# Sheet_BEEE.net
KiCad netlist of a schematic drawn in Altium Designer
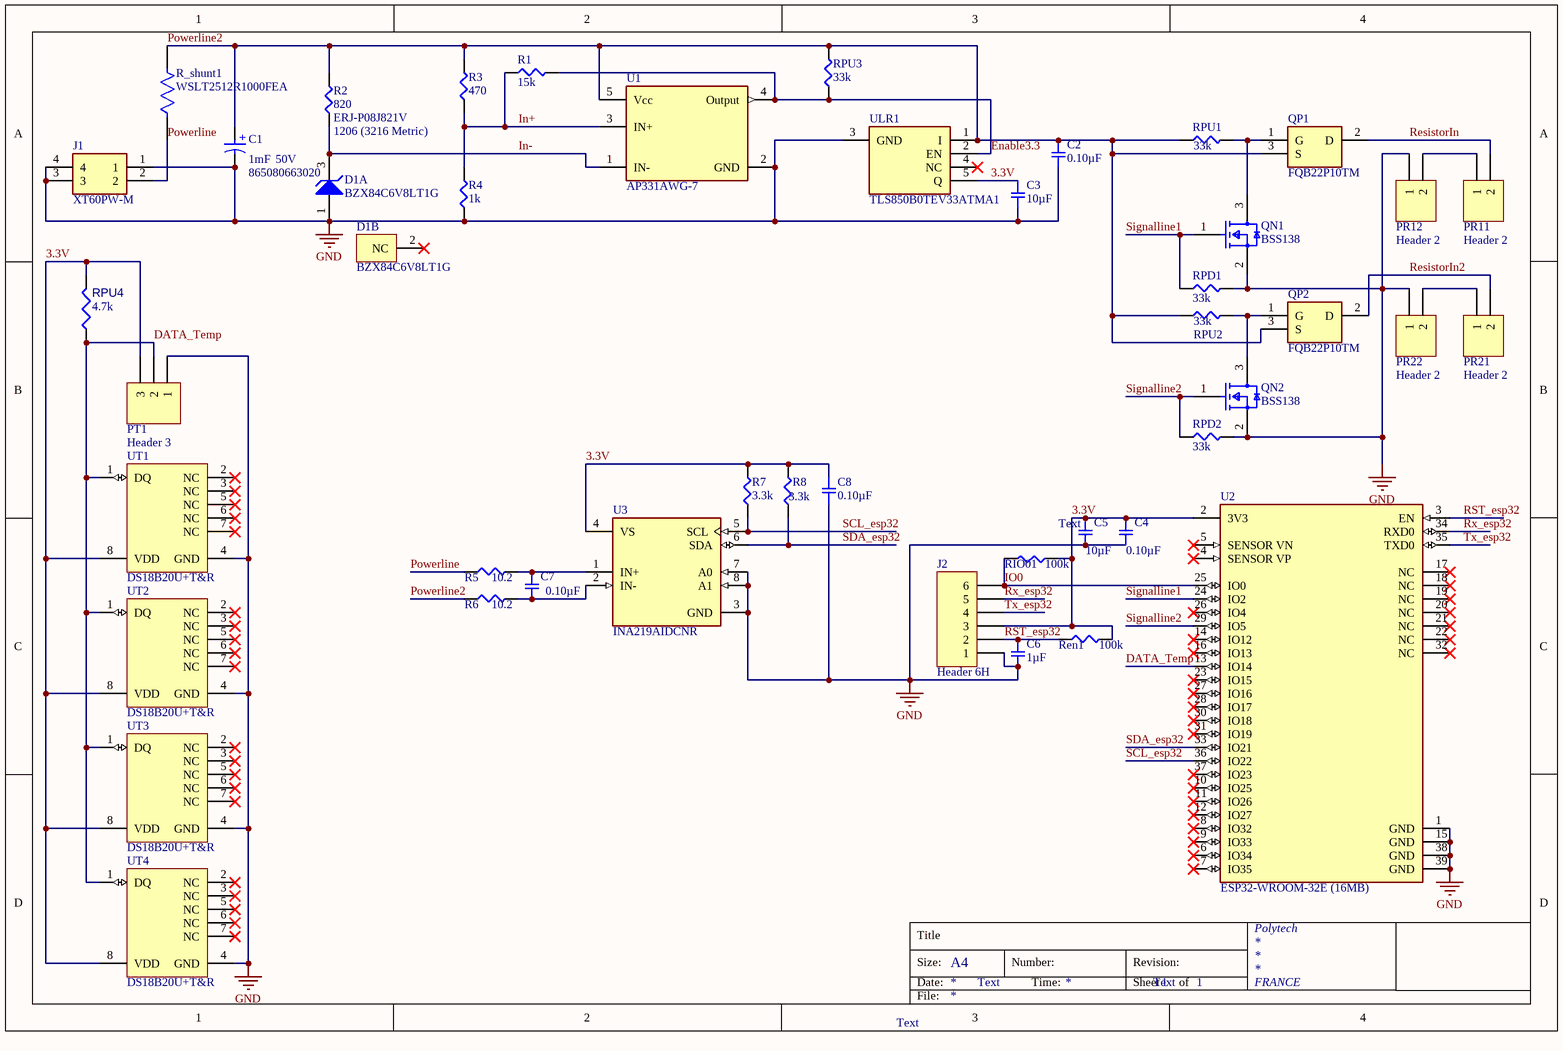
[diagram p0: Sheet_BEEE.SchDoc]

(export (version "E")
  (design (tool "Eeschema 10.0.6"))
  (components
    (comp (ref "C1")
      (value "865080663020")
      (footprint "WCAP-ASLI_D16H17")
      (description "865080663020 WCAP-ASLI Aluminum Electrolytic Capacitors")
      (fields
        (field (name "CAPACITANCE") "1mF")
        (field (name "VOLTAGE RATING") "50V")
        (field (name "TOLERANCE") "20%")
      )
      (libsource (lib "Altium Content Vault") (part "Capacitor_Polarized"))
    )
    (comp (ref "C2")
      (value "0.10µF")
      (footprint "SMD-0805C")
      (description "CAP CER 0.1UF 50V X7R 0805")
      (fields (field (name "MANUFACTURER") "Murata Electronics North America") (field (name "VOLTAGE") "50V"))
      (libsource (lib "XPERT") (part "CAPACITOR"))
    )
    (comp (ref "C3")
      (value "10µF")
      (footprint "SMD-0805C")
      (description "CAP CER 10UF 35V X5R 0805")
      (fields (field (name "DIGI-KEY PART NUMBER") "490-10515-1-ND") (field (name "TOLERANCE") "±20%"))
      (libsource (lib "XPERT") (part "CAPACITOR"))
    )
    (comp (ref "C4")
      (value "0.10µF")
      (footprint "SMD-0805C")
      (description "CAP CER 0.1UF 50V X7R 0805")
      (fields (field (name "MANUFACTURER") "Murata Electronics North America") (field (name "VOLTAGE") "50V"))
      (libsource (lib "XPERT") (part "CAPACITOR"))
    )
    (comp (ref "C5")
      (value "10µF")
      (footprint "SMD-0805C")
      (description "CAP CER 10UF 35V X5R 0805")
      (fields (field (name "DIGI-KEY PART NUMBER") "490-10515-1-ND") (field (name "TOLERANCE") "±20%"))
      (libsource (lib "XPERT") (part "CAPACITOR"))
    )
    (comp (ref "C6")
      (value "1µF")
      (footprint "SMD-0805C")
      (description "CAP CER 1UF 50V X7R 0805")
      (fields
        (field (name "DIGI-KEY PART NUMBER") "490-10924-1-ND")
        (field (name "PART NUMBER") "GRJ21BR71H105KE01L")
      )
      (libsource (lib "XPERT") (part "CAPACITOR"))
    )
    (comp (ref "C7")
      (value "0.10µF")
      (footprint "SMD-0805C")
      (description "CAP CER 0.1UF 50V X7R 0805")
      (fields (field (name "MANUFACTURER") "Murata Electronics North America") (field (name "VOLTAGE") "50V"))
      (libsource (lib "XPERT") (part "CAPACITOR"))
    )
    (comp (ref "C8")
      (value "0.10µF")
      (footprint "SMD-0805C")
      (description "CAP CER 0.1UF 50V X7R 0805")
      (fields (field (name "MANUFACTURER") "Murata Electronics North America") (field (name "VOLTAGE") "50V"))
      (libsource (lib "XPERT") (part "CAPACITOR"))
    )
    (comp (ref "D1")
      (value "BZX84C6V8LT1G")
      (footprint "ONSC-SOT-23-3-318-08_V")
      (description "Zener Voltage Regulator, 225 mW, 3-Pin SOT-23, Pb-Free, Tape and Reel")
      (fields (field (name "MANUFACTURER") "On Semiconductor"))
      (libsource (lib "Altium Content Vault") (part "ONSC-A1K3-3"))
    )
    (comp (ref "J1")
      (value "XT60PW-M")
      (footprint "SamacSys:XT60PWM")
      (description "Connector")
      (libsource (lib "*") (part "XT60PW-M"))
    )
    (comp (ref "J2")
      (value "Header 6H")
      (footprint "HDR1X6H")
      (description "Header, 6-Pin, Right Angle")
      (fields (field (name "PUBLISHER") "Altium Limited"))
      (libsource (lib "Miscellaneous Connectors") (part "Header 6H"))
    )
    (comp (ref "PR11")
      (value "Header 2")
      (footprint "HDR1X2")
      (description "Header, 2-Pin")
      (fields (field (name "PUBLISHER") "Altium Limited"))
      (libsource (lib "Miscellaneous Connectors") (part "Header 2"))
    )
    (comp (ref "PR12")
      (value "Header 2")
      (footprint "HDR1X2")
      (description "Header, 2-Pin")
      (fields (field (name "PUBLISHER") "Altium Limited"))
      (libsource (lib "Miscellaneous Connectors") (part "Header 2"))
    )
    (comp (ref "PR21")
      (value "Header 2")
      (footprint "HDR1X2")
      (description "Header, 2-Pin")
      (fields (field (name "PUBLISHER") "Altium Limited"))
      (libsource (lib "Miscellaneous Connectors") (part "Header 2"))
    )
    (comp (ref "PR22")
      (value "Header 2")
      (footprint "HDR1X2")
      (description "Header, 2-Pin")
      (fields (field (name "PUBLISHER") "Altium Limited"))
      (libsource (lib "Miscellaneous Connectors") (part "Header 2"))
    )
    (comp (ref "PT1")
      (value "Header 3")
      (footprint "HDR1X3")
      (description "Header, 3-Pin")
      (fields (field (name "PUBLISHER") "Altium Limited"))
      (libsource (lib "Miscellaneous Connectors") (part "Header 3"))
    )
    (comp (ref "QN1")
      (value "BSS138")
      (footprint "FP-318-08-IPC_B")
      (description "MOSFET N-CH 50V 220MA SOT-23")
      (libsource (lib "Altium Content Vault") (part "3b9c635fedb024a5347a57b145af9cc"))
    )
    (comp (ref "QN2")
      (value "BSS138")
      (footprint "FP-318-08-IPC_B")
      (description "MOSFET N-CH 50V 220MA SOT-23")
      (libsource (lib "Altium Content Vault") (part "3b9c635fedb024a5347a57b145af9cc"))
    )
    (comp (ref "QP1")
      (value "FQB22P10TM")
      (footprint "SamacSys:FQB22P10TM")
      (description "MOSFET (P-Channel)")
      (fields (field (name "MOUSER PART NUMBER") "512-FQB22P10TM"))
      (libsource (lib "*") (part "FQB22P10TM"))
    )
    (comp (ref "QP2")
      (value "FQB22P10TM")
      (footprint "SamacSys:FQB22P10TM")
      (description "MOSFET (P-Channel)")
      (fields (field (name "MOUSER PART NUMBER") "512-FQB22P10TM"))
      (libsource (lib "*") (part "FQB22P10TM"))
    )
    (comp (ref "R1")
      (value "15k")
      (footprint "SMD-1206-RES")
      (description "RES SMD 15K OHM 5% 2/3W 1206")
      (fields (field (name "TOLERANCE") "±5%") (field (name "PART NUMBER") "ERJ-P08J153V"))
      (libsource (lib "XPERT") (part "0.1 Ohms 1206"))
    )
    (comp (ref "R2")
      (value "820")
      (footprint "SMD-1206-RES")
      (description "RES SMD 820 OHM 5% 2/3W 1206")
      (fields
        (field (name "DIGI-KEY PART NUMBER") "P820ALCT-ND")
        (field (name "TOLERANCE") "±5%")
        (field (name "PART NUMBER") "ERJ-P08J821V")
        (field (name "PACKAGE / CASE") "1206 (3216 Metric)")
      )
      (libsource (lib "XPERT") (part "0.1 Ohms 1206"))
    )
    (comp (ref "R3")
      (value "470")
      (footprint "SMD-1206-RES")
      (description "RES SMD 470 OHM 1% 1/4W 1206")
      (fields (field (name "PART NUMBER") "ERJ-8ENF4700V") (field (name "TOLERANCE") "±1%"))
      (libsource (lib "XPERT") (part "0.1 Ohms 1206"))
    )
    (comp (ref "R4")
      (value "1k")
      (footprint "SMD-1206-RES")
      (description "RES SMD 1K OHM 5% 2/3W 1206")
      (fields (field (name "TOLERANCE") "±5%") (field (name "PART NUMBER") "ERJ-P08J102V"))
      (libsource (lib "XPERT") (part "0.1 Ohms 1206"))
    )
    (comp (ref "R5")
      (value "10.2")
      (footprint "SMD-1206-RES")
      (description "RES SMD 10.2 OHM 1% 1/4W 1206")
      (fields (field (name "TOLERANCE") "±1%") (field (name "PART NUMBER") "ERJ-8ENF10R2V"))
      (libsource (lib "XPERT") (part "0.1 Ohms 1206"))
    )
    (comp (ref "R6")
      (value "10.2")
      (footprint "SMD-1206-RES")
      (description "RES SMD 10.2 OHM 1% 1/4W 1206")
      (fields (field (name "TOLERANCE") "±1%") (field (name "PART NUMBER") "ERJ-8ENF10R2V"))
      (libsource (lib "XPERT") (part "0.1 Ohms 1206"))
    )
    (comp (ref "R7")
      (value "3.3k")
      (footprint "SMD-1206-RES")
      (description "RES SMD 3.3K OHM 5% 1/4W 1206")
      (fields (field (name "TOLERANCE") "±5%") (field (name "DIGI-KEY PART NUMBER") "P3.3KECT-ND"))
      (libsource (lib "XPERT") (part "0.1 Ohms 1206"))
    )
    (comp (ref "R8")
      (value "3.3k")
      (footprint "SMD-1206-RES")
      (description "RES SMD 3.3K OHM 5% 1/4W 1206")
      (fields (field (name "TOLERANCE") "±5%") (field (name "DIGI-KEY PART NUMBER") "P3.3KECT-ND"))
      (libsource (lib "XPERT") (part "0.1 Ohms 1206"))
    )
    (comp (ref "Ren1")
      (value "100k")
      (footprint "SMD-1206-RES")
      (description "RES SMD 100K OHM 5% 2/3W 1206")
      (fields
        (field (name "DIGI-KEY PART NUMBER") "P100KALCT-ND")
        (field (name "PART NUMBER") "ERJ-P08J104V")
      )
      (libsource (lib "XPERT") (part "0.1 Ohms 1206"))
    )
    (comp (ref "RIO01")
      (value "100k")
      (footprint "SMD-1206-RES")
      (description "RES SMD 100K OHM 5% 2/3W 1206")
      (fields
        (field (name "DIGI-KEY PART NUMBER") "P100KALCT-ND")
        (field (name "PART NUMBER") "ERJ-P08J104V")
      )
      (libsource (lib "XPERT") (part "0.1 Ohms 1206"))
    )
    (comp (ref "RPD1")
      (value "33k")
      (footprint "SMD-1206-RES")
      (description "RES SMD 33K OHM 5% 2/3W 1206")
      (fields (field (name "TOLERANCE") "±5%") (field (name "PART NUMBER") "ERJ-P08J333V"))
      (libsource (lib "XPERT") (part "0.1 Ohms 1206"))
    )
    (comp (ref "RPD2")
      (value "33k")
      (footprint "SMD-1206-RES")
      (description "RES SMD 33K OHM 5% 2/3W 1206")
      (fields (field (name "TOLERANCE") "±5%") (field (name "PART NUMBER") "ERJ-P08J333V"))
      (libsource (lib "XPERT") (part "0.1 Ohms 1206"))
    )
    (comp (ref "RPU1")
      (value "33k")
      (footprint "SMD-1206-RES")
      (description "RES SMD 33K OHM 5% 2/3W 1206")
      (fields (field (name "TOLERANCE") "±5%") (field (name "PART NUMBER") "ERJ-P08J333V"))
      (libsource (lib "XPERT") (part "0.1 Ohms 1206"))
    )
    (comp (ref "RPU2")
      (value "33k")
      (footprint "SMD-1206-RES")
      (description "RES SMD 33K OHM 5% 2/3W 1206")
      (fields (field (name "TOLERANCE") "±5%") (field (name "PART NUMBER") "ERJ-P08J333V"))
      (libsource (lib "XPERT") (part "0.1 Ohms 1206"))
    )
    (comp (ref "RPU3")
      (value "33k")
      (footprint "SMD-1206-RES")
      (description "RES SMD 33K OHM 5% 2/3W 1206")
      (fields (field (name "TOLERANCE") "±5%") (field (name "PART NUMBER") "ERJ-P08J333V"))
      (libsource (lib "XPERT") (part "0.1 Ohms 1206"))
    )
    (comp (ref "RPU4")
      (value "4.7k")
      (footprint "RESC3116X70X50ML13T20")
      (description "Chip Resistor, 4.7 KOhm, +/- 1%, 0.25 W, -55 to 155 degC, 1206 (3216 Metric)")
      (fields (field (name "POWER") "250mW") (field (name "TOLERANCE") "1%"))
      (libsource (lib "XPERT") (part "RES-2"))
    )
    (comp (ref "R_shunt1")
      (value "WSLT2512R1000FEA")
      (footprint "FP-WSLT2512-MFG")
      (description "WSLT2512R1000FEA Res Metal Strip 2512 0.1 Ohm 1% 1W ±75ppm/C Pad SMD Automotive T/R")
      (fields (field (name "TOLERANCE") "1%"))
      (libsource (lib "Altium Content Vault") (part "1029c3af85768c4190bb7ad29bc67b5"))
    )
    (comp (ref "U1")
      (value "AP331AWG-7")
      (footprint "FP-SOT25-MFG")
      (description "IC COMPARATOR SGL DIFF SOT-25")
      (fields
        (field (name "MANUFACTURER") "Diodes Inc.")
        (field (name "OCTOPART") "https://octopart.com/ap331awg-7-diodes+inc.-12688108")
      )
      (libsource (lib "Altium Content Vault") (part "84157f6d693ce6938d681314262b7f3"))
    )
    (comp (ref "U2")
      (value "ESP32-WROOM-32E (16MB)")
      (footprint "FP-ESP32-WROOM-32E_16MB-MFG")
      (description "RX TXRX MOD WIFI TRACE ANT SMD")
      (libsource (lib "Altium Content Vault") (part "77f46594ed2a4fcc7e275071e067929"))
    )
    (comp (ref "U3")
      (value "INA219AIDCNR")
      (footprint "FP-DCN0008A-IPC_B")
      (description "IC CURRENT MONITOR 1% SOT23-8")
      (libsource (lib "Altium Content Vault") (part "e16934b8ef90d0e345b266f0ae9cd81"))
    )
    (comp (ref "ULR1")
      (value "TLS850B0TEV33ATMA1")
      (footprint "SamacSys:BTS6143D")
      (description "Integrated Circuit")
      (fields (field (name "MOUSER PART NUMBER") "726-TLS850B0TEV33ATM"))
      (libsource (lib "*") (part "TLS850B0TEV33ATMA1"))
    )
    (comp (ref "UT1")
      (value "DS18B20U+T&R")
      (footprint "MAXM-U8+1_M")
      (fields (field (name "GENERIC PART NUMBER") "DS18B20"))
      (libsource (lib "Altium Content Vault") (part "DS18B20-U8"))
    )
    (comp (ref "UT2")
      (value "DS18B20U+T&R")
      (footprint "MAXM-U8+1_M")
      (fields (field (name "GENERIC PART NUMBER") "DS18B20"))
      (libsource (lib "Altium Content Vault") (part "DS18B20-U8"))
    )
    (comp (ref "UT3")
      (value "DS18B20U+T&R")
      (footprint "MAXM-U8+1_M")
      (fields (field (name "GENERIC PART NUMBER") "DS18B20"))
      (libsource (lib "Altium Content Vault") (part "DS18B20-U8"))
    )
    (comp (ref "UT4")
      (value "DS18B20U+T&R")
      (footprint "MAXM-U8+1_M")
      (fields (field (name "GENERIC PART NUMBER") "DS18B20"))
      (libsource (lib "Altium Content Vault") (part "DS18B20-U8"))
    )
  )
  (nets
    (net (code "1") (name "/3.3V") (class "Default")
      (node (ref "C3") (pin "1") (pinfunction "1_1") (pintype "passive"))
      (node (ref "C4") (pin "1") (pinfunction "1_1") (pintype "passive"))
      (node (ref "C5") (pin "1") (pinfunction "1_1") (pintype "passive"))
      (node (ref "C8") (pin "2") (pinfunction "2_2") (pintype "passive"))
      (node (ref "J2") (pin "3") (pinfunction "3_3") (pintype "passive"))
      (node (ref "PT1") (pin "3") (pinfunction "3_3") (pintype "passive"))
      (node (ref "R7") (pin "2") (pinfunction "2_2") (pintype "passive"))
      (node (ref "R8") (pin "2") (pinfunction "2_2") (pintype "passive"))
      (node (ref "RIO01") (pin "1") (pinfunction "1_1") (pintype "passive"))
      (node (ref "RPU4") (pin "2") (pinfunction "2_2") (pintype "passive"))
      (node (ref "Ren1") (pin "2") (pinfunction "2_2") (pintype "passive"))
      (node (ref "U2") (pin "2") (pinfunction "3V3_2") (pintype "power_in"))
      (node (ref "U3") (pin "4") (pinfunction "VS_4") (pintype "power_in"))
      (node (ref "ULR1") (pin "5") (pinfunction "Q_5") (pintype "passive"))
      (node (ref "UT1") (pin "8") (pinfunction "VDD_8") (pintype "power_in"))
      (node (ref "UT2") (pin "8") (pinfunction "VDD_8") (pintype "power_in"))
      (node (ref "UT3") (pin "8") (pinfunction "VDD_8") (pintype "power_in"))
      (node (ref "UT4") (pin "8") (pinfunction "VDD_8") (pintype "power_in"))
    )
    (net (code "2") (name "/DATA_Temp") (class "Default")
      (node (ref "PT1") (pin "2") (pinfunction "2_2") (pintype "passive"))
      (node (ref "RPU4") (pin "1") (pinfunction "1_1") (pintype "passive"))
      (node (ref "U2") (pin "13") (pinfunction "IO14_13") (pintype "bidirectional"))
      (node (ref "UT1") (pin "1") (pinfunction "DQ_1") (pintype "bidirectional"))
      (node (ref "UT2") (pin "1") (pinfunction "DQ_1") (pintype "bidirectional"))
      (node (ref "UT3") (pin "1") (pinfunction "DQ_1") (pintype "bidirectional"))
      (node (ref "UT4") (pin "1") (pinfunction "DQ_1") (pintype "bidirectional"))
    )
    (net (code "3") (name "/Enable3.3") (class "Default")
      (node (ref "R1") (pin "2") (pinfunction "2_2") (pintype "passive"))
      (node (ref "RPU3") (pin "1") (pinfunction "1_1") (pintype "passive"))
      (node (ref "U1") (pin "4") (pinfunction "Output_4") (pintype "output"))
      (node (ref "ULR1") (pin "2") (pinfunction "EN_2") (pintype "passive"))
    )
    (net (code "4") (name "/IO0") (class "Default")
      (node (ref "J2") (pin "6") (pinfunction "6_6") (pintype "passive"))
      (node (ref "RIO01") (pin "2") (pinfunction "2_2") (pintype "passive"))
      (node (ref "U2") (pin "25") (pinfunction "IO0_25") (pintype "bidirectional"))
    )
    (net (code "5") (name "/In+") (class "Default")
      (node (ref "R1") (pin "1") (pinfunction "1_1") (pintype "passive"))
      (node (ref "R3") (pin "1") (pinfunction "1_1") (pintype "passive"))
      (node (ref "R4") (pin "2") (pinfunction "2_2") (pintype "passive"))
      (node (ref "U1") (pin "3") (pinfunction "IN+_3") (pintype "tri_state"))
    )
    (net (code "6") (name "/In-") (class "Default")
      (node (ref "D1") (pin "3") (pinfunction "K_3") (pintype "passive"))
      (node (ref "R2") (pin "1") (pinfunction "1_1") (pintype "passive"))
      (node (ref "U1") (pin "1") (pinfunction "IN-_1") (pintype "tri_state"))
    )
    (net (code "7") (name "/Powerline") (class "Default")
      (node (ref "J1") (pin "2") (pinfunction "2_2") (pintype "passive"))
      (node (ref "R5") (pin "1") (pinfunction "1_1") (pintype "passive"))
      (node (ref "R_shunt1") (pin "1") (pinfunction "1_1") (pintype "passive"))
    )
    (net (code "8") (name "/Powerline2") (class "Default")
      (node (ref "C1") (pin "1") (pinfunction "P_1") (pintype "passive"))
      (node (ref "C2") (pin "1") (pinfunction "1_1") (pintype "passive"))
      (node (ref "QP1") (pin "3") (pinfunction "S_3") (pintype "passive"))
      (node (ref "QP2") (pin "3") (pinfunction "S_3") (pintype "passive"))
      (node (ref "R2") (pin "2") (pinfunction "2_2") (pintype "passive"))
      (node (ref "R3") (pin "2") (pinfunction "2_2") (pintype "passive"))
      (node (ref "R6") (pin "1") (pinfunction "1_1") (pintype "passive"))
      (node (ref "RPU1") (pin "1") (pinfunction "1_1") (pintype "passive"))
      (node (ref "RPU2") (pin "1") (pinfunction "1_1") (pintype "passive"))
      (node (ref "RPU3") (pin "2") (pinfunction "2_2") (pintype "passive"))
      (node (ref "R_shunt1") (pin "2") (pinfunction "2_2") (pintype "passive"))
      (node (ref "U1") (pin "5") (pinfunction "Vcc_5") (pintype "power_in"))
      (node (ref "ULR1") (pin "1") (pinfunction "I_1") (pintype "passive"))
    )
    (net (code "9") (name "/RST_esp32") (class "Default")
      (node (ref "C6") (pin "1") (pinfunction "1_1") (pintype "passive"))
      (node (ref "J2") (pin "2") (pinfunction "2_2") (pintype "passive"))
      (node (ref "Ren1") (pin "1") (pinfunction "1_1") (pintype "passive"))
      (node (ref "U2") (pin "3") (pinfunction "EN_3") (pintype "input"))
    )
    (net (code "10") (name "/ResistorIn") (class "Default")
      (node (ref "PR11") (pin "2") (pinfunction "2_2") (pintype "passive"))
      (node (ref "QP1") (pin "2") (pinfunction "D_2") (pintype "passive"))
    )
    (net (code "11") (name "/ResistorIn2") (class "Default")
      (node (ref "PR21") (pin "2") (pinfunction "2_2") (pintype "passive"))
      (node (ref "QP2") (pin "2") (pinfunction "D_2") (pintype "passive"))
    )
    (net (code "12") (name "/Rx_esp32") (class "Default")
      (node (ref "J2") (pin "5") (pinfunction "5_5") (pintype "passive"))
      (node (ref "U2") (pin "34") (pinfunction "RXD0_34") (pintype "bidirectional"))
    )
    (net (code "13") (name "/SCL_esp32") (class "Default")
      (node (ref "R7") (pin "1") (pinfunction "1_1") (pintype "passive"))
      (node (ref "U2") (pin "36") (pinfunction "IO22_36") (pintype "bidirectional"))
      (node (ref "U3") (pin "5") (pinfunction "SCL_5") (pintype "input"))
    )
    (net (code "14") (name "/SDA_esp32") (class "Default")
      (node (ref "R8") (pin "1") (pinfunction "1_1") (pintype "passive"))
      (node (ref "U2") (pin "33") (pinfunction "IO21_33") (pintype "bidirectional"))
      (node (ref "U3") (pin "6") (pinfunction "SDA_6") (pintype "bidirectional"))
    )
    (net (code "15") (name "/Signalline1") (class "Default")
      (node (ref "QN1") (pin "1") (pinfunction "G_1") (pintype "passive"))
      (node (ref "RPD1") (pin "1") (pinfunction "1_1") (pintype "passive"))
      (node (ref "U2") (pin "24") (pinfunction "IO2_24") (pintype "bidirectional"))
    )
    (net (code "16") (name "/Signalline2") (class "Default")
      (node (ref "QN2") (pin "1") (pinfunction "G_1") (pintype "passive"))
      (node (ref "RPD2") (pin "1") (pinfunction "1_1") (pintype "passive"))
      (node (ref "U2") (pin "29") (pinfunction "IO5_29") (pintype "bidirectional"))
    )
    (net (code "17") (name "/Tx_esp32") (class "Default")
      (node (ref "J2") (pin "4") (pinfunction "4_4") (pintype "passive"))
      (node (ref "U2") (pin "35") (pinfunction "TXD0_35") (pintype "bidirectional"))
    )
    (net (code "18") (name "GND") (class "Default")
      (node (ref "C1") (pin "2") (pinfunction "N_2") (pintype "passive"))
      (node (ref "C2") (pin "2") (pinfunction "2_2") (pintype "passive"))
      (node (ref "C3") (pin "2") (pinfunction "2_2") (pintype "passive"))
      (node (ref "C4") (pin "2") (pinfunction "2_2") (pintype "passive"))
      (node (ref "C5") (pin "2") (pinfunction "2_2") (pintype "passive"))
      (node (ref "C6") (pin "2") (pinfunction "2_2") (pintype "passive"))
      (node (ref "C8") (pin "1") (pinfunction "1_1") (pintype "passive"))
      (node (ref "D1") (pin "1") (pinfunction "A_1") (pintype "passive"))
      (node (ref "J1") (pin "1") (pinfunction "1_1") (pintype "passive"))
      (node (ref "J1") (pin "3") (pinfunction "3_3") (pintype "passive"))
      (node (ref "J1") (pin "4") (pinfunction "4_4") (pintype "passive"))
      (node (ref "J2") (pin "1") (pinfunction "1_1") (pintype "passive"))
      (node (ref "PR12") (pin "1") (pinfunction "1_1") (pintype "passive"))
      (node (ref "PR22") (pin "1") (pinfunction "1_1") (pintype "passive"))
      (node (ref "PT1") (pin "1") (pinfunction "1_1") (pintype "passive"))
      (node (ref "QN1") (pin "2") (pinfunction "S_2") (pintype "passive"))
      (node (ref "QN2") (pin "2") (pinfunction "S_2") (pintype "passive"))
      (node (ref "R4") (pin "1") (pinfunction "1_1") (pintype "passive"))
      (node (ref "RPD1") (pin "2") (pinfunction "2_2") (pintype "passive"))
      (node (ref "RPD2") (pin "2") (pinfunction "2_2") (pintype "passive"))
      (node (ref "U1") (pin "2") (pinfunction "GND_2") (pintype "power_in"))
      (node (ref "U2") (pin "1") (pinfunction "GND_1") (pintype "power_in"))
      (node (ref "U2") (pin "15") (pinfunction "GND_15") (pintype "power_in"))
      (node (ref "U2") (pin "38") (pinfunction "GND_38") (pintype "power_in"))
      (node (ref "U2") (pin "39") (pinfunction "GND_39") (pintype "power_in"))
      (node (ref "U3") (pin "3") (pinfunction "GND_3") (pintype "power_in"))
      (node (ref "U3") (pin "7") (pinfunction "A0_7") (pintype "input"))
      (node (ref "U3") (pin "8") (pinfunction "A1_8") (pintype "input"))
      (node (ref "ULR1") (pin "3") (pinfunction "GND_3") (pintype "passive"))
      (node (ref "UT1") (pin "4") (pinfunction "GND_4") (pintype "power_in"))
      (node (ref "UT2") (pin "4") (pinfunction "GND_4") (pintype "power_in"))
      (node (ref "UT3") (pin "4") (pinfunction "GND_4") (pintype "power_in"))
      (node (ref "UT4") (pin "4") (pinfunction "GND_4") (pintype "power_in"))
    )
    (net (code "19") (name "Net-(PR11-Pad1)") (class "Default")
      (node (ref "PR11") (pin "1") (pinfunction "1_1") (pintype "passive"))
      (node (ref "PR12") (pin "2") (pinfunction "2_2") (pintype "passive"))
    )
    (net (code "20") (name "Net-(PR21-Pad1)") (class "Default")
      (node (ref "PR21") (pin "1") (pinfunction "1_1") (pintype "passive"))
      (node (ref "PR22") (pin "2") (pinfunction "2_2") (pintype "passive"))
    )
    (net (code "21") (name "Net-(QN1-D)") (class "Default")
      (node (ref "QN1") (pin "3") (pinfunction "D_3") (pintype "passive"))
      (node (ref "QP1") (pin "1") (pinfunction "G_1") (pintype "passive"))
      (node (ref "RPU1") (pin "2") (pinfunction "2_2") (pintype "passive"))
    )
    (net (code "22") (name "Net-(QN2-D)") (class "Default")
      (node (ref "QN2") (pin "3") (pinfunction "D_3") (pintype "passive"))
      (node (ref "QP2") (pin "1") (pinfunction "G_1") (pintype "passive"))
      (node (ref "RPU2") (pin "2") (pinfunction "2_2") (pintype "passive"))
    )
    (net (code "23") (name "Net-(U3-IN+)") (class "Default")
      (node (ref "C7") (pin "1") (pinfunction "1_1") (pintype "passive"))
      (node (ref "R5") (pin "2") (pinfunction "2_2") (pintype "passive"))
      (node (ref "U3") (pin "1") (pinfunction "IN+_1") (pintype "passive"))
    )
    (net (code "24") (name "Net-(U3-IN-)") (class "Default")
      (node (ref "C7") (pin "2") (pinfunction "2_2") (pintype "passive"))
      (node (ref "R6") (pin "2") (pinfunction "2_2") (pintype "passive"))
      (node (ref "U3") (pin "2") (pinfunction "IN-_2") (pintype "input"))
    )
    (net (code "25") (name "unconnected-(D1B-NC-Pad2)") (class "Default")
      (node (ref "D1") (pin "2") (pinfunction "NC_2") (pintype "passive+no_connect"))
    )
    (net (code "26") (name "unconnected-(U2-IO4-Pad26)") (class "Default")
      (node (ref "U2") (pin "26") (pinfunction "IO4_26") (pintype "bidirectional+no_connect"))
    )
    (net (code "27") (name "unconnected-(U2-IO12-Pad14)") (class "Default")
      (node (ref "U2") (pin "14") (pinfunction "IO12_14") (pintype "bidirectional+no_connect"))
    )
    (net (code "28") (name "unconnected-(U2-IO13-Pad16)") (class "Default")
      (node (ref "U2") (pin "16") (pinfunction "IO13_16") (pintype "bidirectional+no_connect"))
    )
    (net (code "29") (name "unconnected-(U2-IO15-Pad23)") (class "Default")
      (node (ref "U2") (pin "23") (pinfunction "IO15_23") (pintype "bidirectional+no_connect"))
    )
    (net (code "30") (name "unconnected-(U2-IO16-Pad27)") (class "Default")
      (node (ref "U2") (pin "27") (pinfunction "IO16_27") (pintype "bidirectional+no_connect"))
    )
    (net (code "31") (name "unconnected-(U2-IO17-Pad28)") (class "Default")
      (node (ref "U2") (pin "28") (pinfunction "IO17_28") (pintype "bidirectional+no_connect"))
    )
    (net (code "32") (name "unconnected-(U2-IO18-Pad30)") (class "Default")
      (node (ref "U2") (pin "30") (pinfunction "IO18_30") (pintype "bidirectional+no_connect"))
    )
    (net (code "33") (name "unconnected-(U2-IO19-Pad31)") (class "Default")
      (node (ref "U2") (pin "31") (pinfunction "IO19_31") (pintype "bidirectional+no_connect"))
    )
    (net (code "34") (name "unconnected-(U2-IO23-Pad37)") (class "Default")
      (node (ref "U2") (pin "37") (pinfunction "IO23_37") (pintype "bidirectional+no_connect"))
    )
    (net (code "35") (name "unconnected-(U2-IO25-Pad10)") (class "Default")
      (node (ref "U2") (pin "10") (pinfunction "IO25_10") (pintype "bidirectional+no_connect"))
    )
    (net (code "36") (name "unconnected-(U2-IO26-Pad11)") (class "Default")
      (node (ref "U2") (pin "11") (pinfunction "IO26_11") (pintype "bidirectional+no_connect"))
    )
    (net (code "37") (name "unconnected-(U2-IO27-Pad12)") (class "Default")
      (node (ref "U2") (pin "12") (pinfunction "IO27_12") (pintype "bidirectional+no_connect"))
    )
    (net (code "38") (name "unconnected-(U2-IO32-Pad8)") (class "Default")
      (node (ref "U2") (pin "8") (pinfunction "IO32_8") (pintype "bidirectional+no_connect"))
    )
    (net (code "39") (name "unconnected-(U2-IO33-Pad9)") (class "Default")
      (node (ref "U2") (pin "9") (pinfunction "IO33_9") (pintype "bidirectional+no_connect"))
    )
    (net (code "40") (name "unconnected-(U2-IO34-Pad6)") (class "Default")
      (node (ref "U2") (pin "6") (pinfunction "IO34_6") (pintype "bidirectional+no_connect"))
    )
    (net (code "41") (name "unconnected-(U2-IO35-Pad7)") (class "Default")
      (node (ref "U2") (pin "7") (pinfunction "IO35_7") (pintype "bidirectional+no_connect"))
    )
    (net (code "42") (name "unconnected-(U2-NC-Pad17)") (class "Default")
      (node (ref "U2") (pin "17") (pinfunction "NC_17") (pintype "passive+no_connect"))
    )
    (net (code "43") (name "unconnected-(U2-NC-Pad18)") (class "Default")
      (node (ref "U2") (pin "18") (pinfunction "NC_18") (pintype "passive+no_connect"))
    )
    (net (code "44") (name "unconnected-(U2-NC-Pad19)") (class "Default")
      (node (ref "U2") (pin "19") (pinfunction "NC_19") (pintype "passive+no_connect"))
    )
    (net (code "45") (name "unconnected-(U2-NC-Pad20)") (class "Default")
      (node (ref "U2") (pin "20") (pinfunction "NC_20") (pintype "passive+no_connect"))
    )
    (net (code "46") (name "unconnected-(U2-NC-Pad21)") (class "Default")
      (node (ref "U2") (pin "21") (pinfunction "NC_21") (pintype "passive+no_connect"))
    )
    (net (code "47") (name "unconnected-(U2-NC-Pad22)") (class "Default")
      (node (ref "U2") (pin "22") (pinfunction "NC_22") (pintype "passive+no_connect"))
    )
    (net (code "48") (name "unconnected-(U2-NC-Pad32)") (class "Default")
      (node (ref "U2") (pin "32") (pinfunction "NC_32") (pintype "passive+no_connect"))
    )
    (net (code "49") (name "unconnected-(U2-SENSOR_VN-Pad5)") (class "Default")
      (node (ref "U2") (pin "5") (pinfunction "SENSOR_VN_5") (pintype "input+no_connect"))
    )
    (net (code "50") (name "unconnected-(U2-SENSOR_VP-Pad4)") (class "Default")
      (node (ref "U2") (pin "4") (pinfunction "SENSOR_VP_4") (pintype "input+no_connect"))
    )
    (net (code "51") (name "unconnected-(ULR1-NC-Pad4)") (class "Default")
      (node (ref "ULR1") (pin "4") (pinfunction "NC_4") (pintype "passive+no_connect"))
    )
    (net (code "52") (name "unconnected-(UT1-NC-Pad2)") (class "Default")
      (node (ref "UT1") (pin "2") (pinfunction "NC_2") (pintype "passive+no_connect"))
    )
    (net (code "53") (name "unconnected-(UT1-NC-Pad3)") (class "Default")
      (node (ref "UT1") (pin "3") (pinfunction "NC_3") (pintype "passive+no_connect"))
    )
    (net (code "54") (name "unconnected-(UT1-NC-Pad5)") (class "Default")
      (node (ref "UT1") (pin "5") (pinfunction "NC_5") (pintype "passive+no_connect"))
    )
    (net (code "55") (name "unconnected-(UT1-NC-Pad6)") (class "Default")
      (node (ref "UT1") (pin "6") (pinfunction "NC_6") (pintype "passive+no_connect"))
    )
    (net (code "56") (name "unconnected-(UT1-NC-Pad7)") (class "Default")
      (node (ref "UT1") (pin "7") (pinfunction "NC_7") (pintype "passive+no_connect"))
    )
    (net (code "57") (name "unconnected-(UT2-NC-Pad2)") (class "Default")
      (node (ref "UT2") (pin "2") (pinfunction "NC_2") (pintype "passive+no_connect"))
    )
    (net (code "58") (name "unconnected-(UT2-NC-Pad3)") (class "Default")
      (node (ref "UT2") (pin "3") (pinfunction "NC_3") (pintype "passive+no_connect"))
    )
    (net (code "59") (name "unconnected-(UT2-NC-Pad5)") (class "Default")
      (node (ref "UT2") (pin "5") (pinfunction "NC_5") (pintype "passive+no_connect"))
    )
    (net (code "60") (name "unconnected-(UT2-NC-Pad6)") (class "Default")
      (node (ref "UT2") (pin "6") (pinfunction "NC_6") (pintype "passive+no_connect"))
    )
    (net (code "61") (name "unconnected-(UT2-NC-Pad7)") (class "Default")
      (node (ref "UT2") (pin "7") (pinfunction "NC_7") (pintype "passive+no_connect"))
    )
    (net (code "62") (name "unconnected-(UT3-NC-Pad2)") (class "Default")
      (node (ref "UT3") (pin "2") (pinfunction "NC_2") (pintype "passive+no_connect"))
    )
    (net (code "63") (name "unconnected-(UT3-NC-Pad3)") (class "Default")
      (node (ref "UT3") (pin "3") (pinfunction "NC_3") (pintype "passive+no_connect"))
    )
    (net (code "64") (name "unconnected-(UT3-NC-Pad5)") (class "Default")
      (node (ref "UT3") (pin "5") (pinfunction "NC_5") (pintype "passive+no_connect"))
    )
    (net (code "65") (name "unconnected-(UT3-NC-Pad6)") (class "Default")
      (node (ref "UT3") (pin "6") (pinfunction "NC_6") (pintype "passive+no_connect"))
    )
    (net (code "66") (name "unconnected-(UT3-NC-Pad7)") (class "Default")
      (node (ref "UT3") (pin "7") (pinfunction "NC_7") (pintype "passive+no_connect"))
    )
    (net (code "67") (name "unconnected-(UT4-NC-Pad2)") (class "Default")
      (node (ref "UT4") (pin "2") (pinfunction "NC_2") (pintype "passive+no_connect"))
    )
    (net (code "68") (name "unconnected-(UT4-NC-Pad3)") (class "Default")
      (node (ref "UT4") (pin "3") (pinfunction "NC_3") (pintype "passive+no_connect"))
    )
    (net (code "69") (name "unconnected-(UT4-NC-Pad5)") (class "Default")
      (node (ref "UT4") (pin "5") (pinfunction "NC_5") (pintype "passive+no_connect"))
    )
    (net (code "70") (name "unconnected-(UT4-NC-Pad6)") (class "Default")
      (node (ref "UT4") (pin "6") (pinfunction "NC_6") (pintype "passive+no_connect"))
    )
    (net (code "71") (name "unconnected-(UT4-NC-Pad7)") (class "Default")
      (node (ref "UT4") (pin "7") (pinfunction "NC_7") (pintype "passive+no_connect"))
    )
  )
)
